# Sheet2.net
KiCad netlist of a schematic drawn in Altium Designer
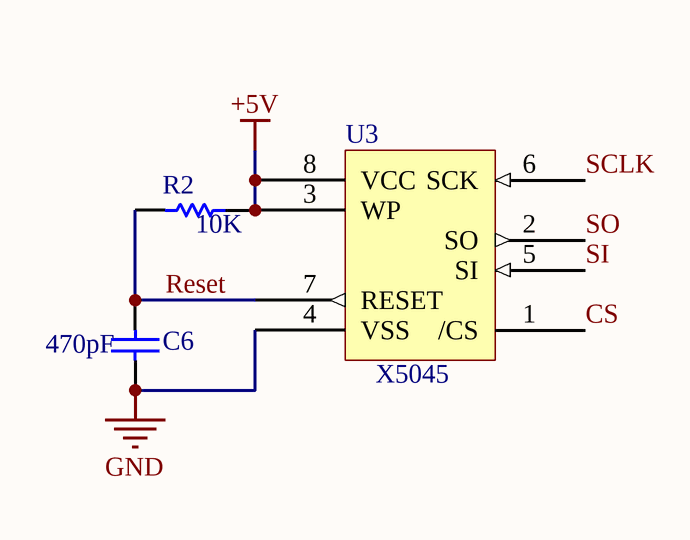
[diagram p0: Sheet2.SchDoc]

(export (version "E")
  (design (tool "Eeschema 10.0.6"))
  (components
    (comp (ref "C6")
      (value "470pF")
      (footprint "RAD-0.3")
      (description "Capacitor")
      (fields (field (name "Comment") "Cap") (field (name "PUBLISHER") "Altium Limited"))
      (libsource (lib "Miscellaneous Devices") (part "Cap"))
    )
    (comp (ref "R2")
      (value "10K")
      (footprint "AXIAL-0.3")
      (description "Resistor")
      (fields (field (name "Comment") "10k") (field (name "PUBLISHER") "Altium Limited"))
      (libsource (lib "Miscellaneous Devices") (part "Res1"))
    )
    (comp (ref "U3")
      (value "X5045")
      (footprint "DIP8")
      (description "EEPROM+Watchdog")
      (libsource (lib "存储器") (part "X5045"))
    )
  )
  (nets
    (net (code "1") (name "+5V") (class "Default")
      (node (ref "R2") (pin "1") (pinfunction "1_1") (pintype "passive"))
      (node (ref "U3") (pin "3") (pinfunction "WP_3") (pintype "passive"))
      (node (ref "U3") (pin "8") (pinfunction "VCC_8") (pintype "power_in"))
    )
    (net (code "2") (name "/CS") (class "Default")
      (node (ref "U3") (pin "1") (pinfunction "/CS_1") (pintype "passive"))
    )
    (net (code "3") (name "/Reset") (class "Default")
      (node (ref "C6") (pin "1") (pinfunction "1_1") (pintype "passive"))
      (node (ref "R2") (pin "2") (pinfunction "2_2") (pintype "passive"))
      (node (ref "U3") (pin "7") (pinfunction "RESET_7") (pintype "output"))
    )
    (net (code "4") (name "/SCLK") (class "Default")
      (node (ref "U3") (pin "6") (pinfunction "SCK_6") (pintype "input"))
    )
    (net (code "5") (name "/SI") (class "Default")
      (node (ref "U3") (pin "5") (pinfunction "SI_5") (pintype "input"))
    )
    (net (code "6") (name "/SO") (class "Default")
      (node (ref "U3") (pin "2") (pinfunction "SO_2") (pintype "output"))
    )
    (net (code "7") (name "GND") (class "Default")
      (node (ref "C6") (pin "2") (pinfunction "2_2") (pintype "passive"))
      (node (ref "U3") (pin "4") (pinfunction "VSS_4") (pintype "power_in"))
    )
  )
)
